# tl4242-driver-20mm-mk-1.net
KiCad netlist of a schematic drawn in EAGLE
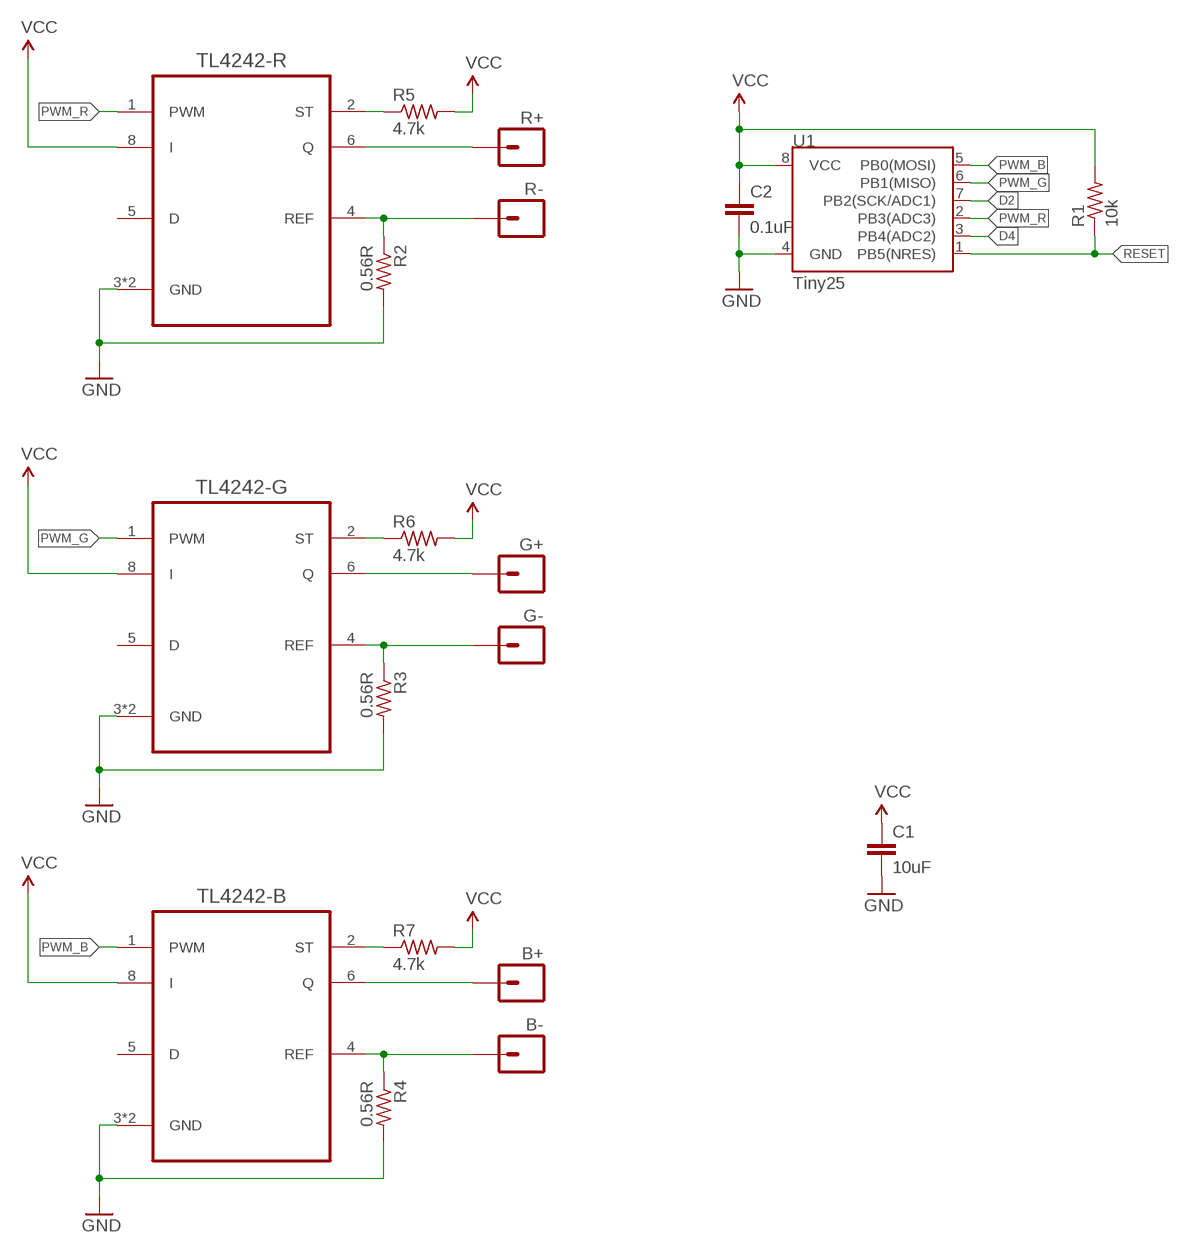
[diagram p0: schematic, sheet 1]

(export (version "E")
  (design (tool "Eeschema 10.0.6"))
  (components
    (comp (ref "B+")
      (value "M01PTH-0.65MM-NS")
      (footprint "eagle-import:1X01_635UM")
      (libsource (lib "eagle-import") (part "M01PTH-0.65MM-NS"))
    )
    (comp (ref "B-")
      (value "M01PTH-0.65MM-NS")
      (footprint "eagle-import:1X01_635UM")
      (libsource (lib "eagle-import") (part "M01PTH-0.65MM-NS"))
    )
    (comp (ref "C1")
      (value "10uF")
      (footprint "eagle-import:C0805")
      (libsource (lib "eagle-import") (part "CAPACITOR-CERAMICC0805"))
    )
    (comp (ref "C2")
      (value "0.1uF")
      (footprint "eagle-import:C0603")
      (libsource (lib "eagle-import") (part "CAPACITOR-CERAMICC0603"))
    )
    (comp (ref "G+")
      (value "M01PTH-0.65MM-NS")
      (footprint "eagle-import:1X01_635UM")
      (libsource (lib "eagle-import") (part "M01PTH-0.65MM-NS"))
    )
    (comp (ref "G-")
      (value "M01PTH-0.65MM-NS")
      (footprint "eagle-import:1X01_635UM")
      (libsource (lib "eagle-import") (part "M01PTH-0.65MM-NS"))
    )
    (comp (ref "R+")
      (value "M01PTH-0.65MM-NS")
      (footprint "eagle-import:1X01_635UM")
      (libsource (lib "eagle-import") (part "M01PTH-0.65MM-NS"))
    )
    (comp (ref "R-")
      (value "M01PTH-0.65MM-NS")
      (footprint "eagle-import:1X01_635UM")
      (libsource (lib "eagle-import") (part "M01PTH-0.65MM-NS"))
    )
    (comp (ref "R1")
      (value "10k")
      (footprint "eagle-import:R0603")
      (libsource (lib "eagle-import") (part "RESISTORR0603"))
    )
    (comp (ref "R2")
      (value "0.56R")
      (footprint "eagle-import:R1206")
      (libsource (lib "eagle-import") (part "RESISTORR1206"))
    )
    (comp (ref "R3")
      (value "0.56R")
      (footprint "eagle-import:R1206")
      (libsource (lib "eagle-import") (part "RESISTORR1206"))
    )
    (comp (ref "R4")
      (value "0.56R")
      (footprint "eagle-import:R1206")
      (libsource (lib "eagle-import") (part "RESISTORR1206"))
    )
    (comp (ref "R5")
      (value "4.7k")
      (footprint "eagle-import:R0402")
      (libsource (lib "eagle-import") (part "RESISTORR0402"))
    )
    (comp (ref "R6")
      (value "4.7k")
      (footprint "eagle-import:R0402")
      (libsource (lib "eagle-import") (part "RESISTORR0402"))
    )
    (comp (ref "R7")
      (value "4.7k")
      (footprint "eagle-import:R0402")
      (libsource (lib "eagle-import") (part "RESISTORR0402"))
    )
    (comp (ref "TL4242-B")
      (value "TL4242DRJRSON8")
      (footprint "eagle-import:SON80P410X410X80-9N")
      (fields (field (name "MPN") "TL4242DRJR"))
      (libsource (lib "eagle-import") (part "TL4242DRJRSON8"))
    )
    (comp (ref "TL4242-G")
      (value "TL4242DRJRSON8")
      (footprint "eagle-import:SON80P410X410X80-9N")
      (fields (field (name "MPN") "TL4242DRJR"))
      (libsource (lib "eagle-import") (part "TL4242DRJRSON8"))
    )
    (comp (ref "TL4242-R")
      (value "TL4242DRJRSON8")
      (footprint "eagle-import:SON80P410X410X80-9N")
      (fields (field (name "MPN") "TL4242DRJR"))
      (libsource (lib "eagle-import") (part "TL4242DRJRSON8"))
    )
    (comp (ref "U1")
      (value "Tiny25")
      (footprint "eagle-import:SO08")
      (libsource (lib "eagle-import") (part "ATTINY45TINY25-20-SOICN"))
    )
  )
  (nets
    (net (code "1") (name "D2") (class "Default")
      (node (ref "U1") (pin "7") (pinfunction "PB2(SCK/ADC1)_7") (pintype "bidirectional"))
    )
    (net (code "2") (name "D4") (class "Default")
      (node (ref "U1") (pin "3") (pinfunction "PB4(ADC2)_3") (pintype "bidirectional"))
    )
    (net (code "3") (name "GND") (class "Default")
      (node (ref "C1") (pin "2") (pinfunction "2_2") (pintype "passive"))
      (node (ref "C2") (pin "2") (pinfunction "2_2") (pintype "passive"))
      (node (ref "R2") (pin "2") (pinfunction "2_2") (pintype "passive"))
      (node (ref "R3") (pin "2") (pinfunction "2_2") (pintype "passive"))
      (node (ref "R4") (pin "2") (pinfunction "2_2") (pintype "passive"))
      (node (ref "TL4242-B") (pin "3") (pinfunction "GND_3") (pintype "passive"))
      (node (ref "TL4242-B") (pin "9") (pinfunction "GND_9") (pintype "passive"))
      (node (ref "TL4242-G") (pin "3") (pinfunction "GND_3") (pintype "passive"))
      (node (ref "TL4242-G") (pin "9") (pinfunction "GND_9") (pintype "passive"))
      (node (ref "TL4242-R") (pin "3") (pinfunction "GND_3") (pintype "passive"))
      (node (ref "TL4242-R") (pin "9") (pinfunction "GND_9") (pintype "passive"))
      (node (ref "U1") (pin "4") (pinfunction "GND_4") (pintype "bidirectional"))
    )
    (net (code "4") (name "Net-(B+-1)") (class "Default")
      (node (ref "B+") (pin "P$1") (pinfunction "1_P$1") (pintype "passive"))
      (node (ref "TL4242-B") (pin "6") (pinfunction "Q_6") (pintype "output"))
    )
    (net (code "5") (name "Net-(B--1)") (class "Default")
      (node (ref "B-") (pin "P$1") (pinfunction "1_P$1") (pintype "passive"))
      (node (ref "R4") (pin "1") (pinfunction "1_1") (pintype "passive"))
      (node (ref "TL4242-B") (pin "4") (pinfunction "REF_4") (pintype "input"))
    )
    (net (code "6") (name "Net-(G+-1)") (class "Default")
      (node (ref "G+") (pin "P$1") (pinfunction "1_P$1") (pintype "passive"))
      (node (ref "TL4242-G") (pin "6") (pinfunction "Q_6") (pintype "output"))
    )
    (net (code "7") (name "Net-(G--1)") (class "Default")
      (node (ref "G-") (pin "P$1") (pinfunction "1_P$1") (pintype "passive"))
      (node (ref "R3") (pin "1") (pinfunction "1_1") (pintype "passive"))
      (node (ref "TL4242-G") (pin "4") (pinfunction "REF_4") (pintype "input"))
    )
    (net (code "8") (name "Net-(R+-1)") (class "Default")
      (node (ref "R+") (pin "P$1") (pinfunction "1_P$1") (pintype "passive"))
      (node (ref "TL4242-R") (pin "6") (pinfunction "Q_6") (pintype "output"))
    )
    (net (code "9") (name "Net-(R--1)") (class "Default")
      (node (ref "R-") (pin "P$1") (pinfunction "1_P$1") (pintype "passive"))
      (node (ref "R2") (pin "1") (pinfunction "1_1") (pintype "passive"))
      (node (ref "TL4242-R") (pin "4") (pinfunction "REF_4") (pintype "input"))
    )
    (net (code "10") (name "Net-(TL4242-B-ST)") (class "Default")
      (node (ref "R7") (pin "1") (pinfunction "1_1") (pintype "passive"))
      (node (ref "TL4242-B") (pin "2") (pinfunction "ST_2") (pintype "output"))
    )
    (net (code "11") (name "Net-(TL4242-G-ST)") (class "Default")
      (node (ref "R6") (pin "1") (pinfunction "1_1") (pintype "passive"))
      (node (ref "TL4242-G") (pin "2") (pinfunction "ST_2") (pintype "output"))
    )
    (net (code "12") (name "Net-(TL4242-R-ST)") (class "Default")
      (node (ref "R5") (pin "1") (pinfunction "1_1") (pintype "passive"))
      (node (ref "TL4242-R") (pin "2") (pinfunction "ST_2") (pintype "output"))
    )
    (net (code "13") (name "PWM_B") (class "Default")
      (node (ref "TL4242-B") (pin "1") (pinfunction "PWM_1") (pintype "input"))
      (node (ref "U1") (pin "5") (pinfunction "PB0(MOSI)_5") (pintype "bidirectional"))
    )
    (net (code "14") (name "PWM_G") (class "Default")
      (node (ref "TL4242-G") (pin "1") (pinfunction "PWM_1") (pintype "input"))
      (node (ref "U1") (pin "6") (pinfunction "PB1(MISO)_6") (pintype "bidirectional"))
    )
    (net (code "15") (name "PWM_R") (class "Default")
      (node (ref "TL4242-R") (pin "1") (pinfunction "PWM_1") (pintype "input"))
      (node (ref "U1") (pin "2") (pinfunction "PB3(ADC3)_2") (pintype "bidirectional"))
    )
    (net (code "16") (name "RESET") (class "Default")
      (node (ref "R1") (pin "1") (pinfunction "1_1") (pintype "passive"))
      (node (ref "U1") (pin "1") (pinfunction "PB5(NRES)_1") (pintype "bidirectional"))
    )
    (net (code "17") (name "VCC") (class "Default")
      (node (ref "C1") (pin "1") (pinfunction "1_1") (pintype "passive"))
      (node (ref "C2") (pin "1") (pinfunction "1_1") (pintype "passive"))
      (node (ref "R1") (pin "2") (pinfunction "2_2") (pintype "passive"))
      (node (ref "R5") (pin "2") (pinfunction "2_2") (pintype "passive"))
      (node (ref "R6") (pin "2") (pinfunction "2_2") (pintype "passive"))
      (node (ref "R7") (pin "2") (pinfunction "2_2") (pintype "passive"))
      (node (ref "TL4242-B") (pin "8") (pinfunction "I_8") (pintype "input"))
      (node (ref "TL4242-G") (pin "8") (pinfunction "I_8") (pintype "input"))
      (node (ref "TL4242-R") (pin "8") (pinfunction "I_8") (pintype "input"))
      (node (ref "U1") (pin "8") (pinfunction "VCC_8") (pintype "bidirectional"))
    )
    (net (code "18") (name "unconnected-(TL4242-B-D-Pad5)") (class "Default")
      (node (ref "TL4242-B") (pin "5") (pinfunction "D_5") (pintype "input"))
    )
    (net (code "19") (name "unconnected-(TL4242-G-D-Pad5)") (class "Default")
      (node (ref "TL4242-G") (pin "5") (pinfunction "D_5") (pintype "input"))
    )
    (net (code "20") (name "unconnected-(TL4242-R-D-Pad5)") (class "Default")
      (node (ref "TL4242-R") (pin "5") (pinfunction "D_5") (pintype "input"))
    )
  )
)
